# DSD_SDR_MainBoard_Simple.net
KiCad netlist of a schematic drawn in Altium Designer
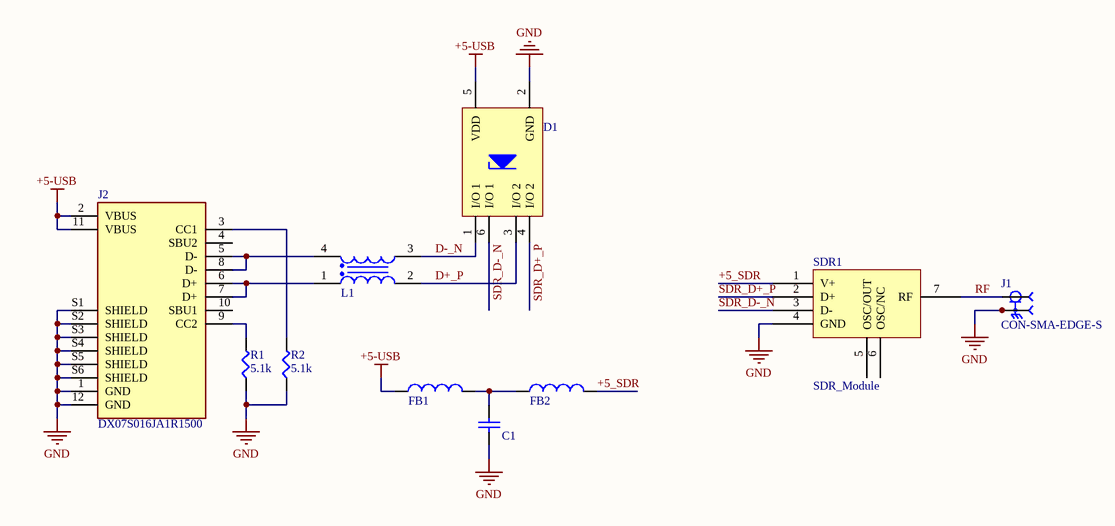
[diagram p0: DSD_SDR_MainBoard_Simple.SchDoc]

(export (version "E")
  (design (tool "Eeschema 10.0.6"))
  (components
    (comp (ref "C1")
      (value "680nF")
      (footprint "WCAP-CSGP_0603_L1.6W0.8H0.8_Reflow")
      (description "WCAP-CSGP Multilayer Ceramic Chip Capacitor, General Purpose, size 0603, X7R, 680nF, 16VDC")
      (fields
        (field (name "MANUFACTURER PART NUMBER") "885012206051")
        (field (name "MANUFACTURER") "Wurth Elektronik")
      )
      (libsource (lib "Altium_WCAP-CSGP (rev22f)") (part "885012206051"))
    )
    (comp (ref "D1")
      (value "5V")
      (footprint "WE-TVS_SOT23-6L")
      (description "WE-TVS TVS Diode – High Speed Series, SOT23-6L, 2+1 Channel, 5V, 2pF")
      (fields
        (field (name "MANUFACTURER PART NUMBER") "82400102")
        (field (name "MANUFACTURER") "Wurth Elektronik")
      )
      (libsource (lib "Altium_WE-TVS (rev22b)") (part "82400102"))
    )
    (comp (ref "FB1")
      (value "600Ohm")
      (footprint "WE-CBF_0603_L1.6W0.8H0.8_HC")
      (description "WE-CBF SMT EMI Suppression Ferrite Bead, size 0603, 600Ohm, 1A")
      (fields
        (field (name "MANUFACTURER PART NUMBER") "742792651")
        (field (name "MANUFACTURER") "Wurth Elektronik")
      )
      (libsource (lib "WE-CBF (rev22d)") (part "742792651"))
    )
    (comp (ref "FB2")
      (value "600Ohm")
      (footprint "WE-CBF_0603_L1.6W0.8H0.8_HC")
      (description "WE-CBF SMT EMI Suppression Ferrite Bead, size 0603, 600Ohm, 1A")
      (fields
        (field (name "MANUFACTURER PART NUMBER") "742792651")
        (field (name "MANUFACTURER") "Wurth Elektronik")
      )
      (libsource (lib "WE-CBF (rev22d)") (part "742792651"))
    )
    (comp (ref "J1")
      (value "CON-SMA-EDGE-S")
      (footprint "RFSOLUTIONS_CON-SMA-EDGE-S")
      (description "SMA Connector Jack, Female Socket - Board Edge, End Launch Solder")
      (fields (field (name "MF") "RF Solutions") (field (name "DIGI-KEY_PART_NUMBER") "CON-SMA-EDGE-S-ND"))
      (libsource (lib "CON-SMA-EDGE-S") (part "CON-SMA-EDGE-S"))
    )
    (comp (ref "J2")
      (value "DX07S016JA1R1500")
      (footprint "JAE_DX07S016JA1R1500")
      (fields (field (name "MF") "JAE Electronics"))
      (libsource (lib "DX07S016JA1R1500") (part "DX07S016JA1R1500"))
    )
    (comp (ref "L1")
      (value "90Ohm")
      (footprint "WE-CNSW_1206")
      (description "WE-CNSW SMT Common Mode Line Filter, size 1206, 90Ohm, 0.111uH, 50V")
      (fields
        (field (name "MANUFACTURER") "Wurth Elektronik")
        (field (name "MANUFACTURER PART NUMBER") "744232090")
      )
      (libsource (lib "WE-CNSW (rev22a)") (part "744232090"))
    )
    (comp (ref "R1")
      (value "5.1k")
      (footprint "SMD-0603-RES")
      (description "RES SMD 5.1K OHM 1% 1/10W 0603")
      (fields
        (field (name "PART NUMBER") "ERJ-3EKF5101V")
        (field (name "DIGI-KEY PART NUMBER") "P5.10KHCT-ND")
      )
      (libsource (lib "res_panasonic_erj_xls") (part "RESISTOR"))
    )
    (comp (ref "R2")
      (value "5.1k")
      (footprint "SMD-0603-RES")
      (description "RES SMD 5.1K OHM 1% 1/10W 0603")
      (fields
        (field (name "PART NUMBER") "ERJ-3EKF5101V")
        (field (name "DIGI-KEY PART NUMBER") "P5.10KHCT-ND")
      )
      (libsource (lib "res_panasonic_erj_xls") (part "RESISTOR"))
    )
    (comp (ref "SDR1")
      (value "SDR_Module")
      (footprint "SDR")
      (libsource (lib "SDR_Module") (part "SDR_Module"))
    )
  )
  (nets
    (net (code "1") (name "+5-USB") (class "Default")
      (node (ref "D1") (pin "5") (pinfunction "VDD_5") (pintype "passive"))
      (node (ref "FB1") (pin "1") (pinfunction "1_1") (pintype "passive"))
      (node (ref "J2") (pin "11") (pinfunction "VBUS_11") (pintype "power_in"))
      (node (ref "J2") (pin "2") (pinfunction "VBUS_2") (pintype "power_in"))
    )
    (net (code "2") (name "/+5_SDR") (class "Default")
      (node (ref "FB2") (pin "2") (pinfunction "2_2") (pintype "passive"))
      (node (ref "SDR1") (pin "1") (pinfunction "V+_1") (pintype "passive"))
    )
    (net (code "3") (name "/D+_P") (class "Default")
      (node (ref "D1") (pin "3") (pinfunction "I/O_2_3") (pintype "passive"))
      (node (ref "L1") (pin "2") (pinfunction "2_2") (pintype "passive"))
    )
    (net (code "4") (name "/D-_N") (class "Default")
      (node (ref "D1") (pin "1") (pinfunction "I/O_1_1") (pintype "passive"))
      (node (ref "L1") (pin "3") (pinfunction "3_3") (pintype "passive"))
    )
    (net (code "5") (name "/RF") (class "Default")
      (node (ref "J1") (pin "1") (pinfunction "1_1") (pintype "passive"))
      (node (ref "SDR1") (pin "7") (pinfunction "RF_7") (pintype "passive"))
    )
    (net (code "6") (name "/SDR_D+_P") (class "Default")
      (node (ref "D1") (pin "4") (pinfunction "I/O_2_4") (pintype "passive"))
      (node (ref "SDR1") (pin "2") (pinfunction "D+_2") (pintype "passive"))
    )
    (net (code "7") (name "/SDR_D-_N") (class "Default")
      (node (ref "D1") (pin "6") (pinfunction "I/O_1_6") (pintype "passive"))
      (node (ref "SDR1") (pin "3") (pinfunction "D-_3") (pintype "passive"))
    )
    (net (code "8") (name "GND") (class "Default")
      (node (ref "C1") (pin "1") (pinfunction "1_1") (pintype "passive"))
      (node (ref "D1") (pin "2") (pinfunction "GND_2") (pintype "passive"))
      (node (ref "J1") (pin "G1") (pinfunction "2_G1") (pintype "passive"))
      (node (ref "J1") (pin "G2") (pinfunction "2_G2") (pintype "passive"))
      (node (ref "J1") (pin "G3") (pinfunction "2_G3") (pintype "passive"))
      (node (ref "J1") (pin "G4") (pinfunction "2_G4") (pintype "passive"))
      (node (ref "J2") (pin "1") (pinfunction "GND_1") (pintype "power_in"))
      (node (ref "J2") (pin "12") (pinfunction "GND_12") (pintype "power_in"))
      (node (ref "J2") (pin "S1") (pinfunction "SHIELD_S1") (pintype "passive"))
      (node (ref "J2") (pin "S2") (pinfunction "SHIELD_S2") (pintype "passive"))
      (node (ref "J2") (pin "S3") (pinfunction "SHIELD_S3") (pintype "passive"))
      (node (ref "J2") (pin "S4") (pinfunction "SHIELD_S4") (pintype "passive"))
      (node (ref "J2") (pin "S5") (pinfunction "SHIELD_S5") (pintype "passive"))
      (node (ref "J2") (pin "S6") (pinfunction "SHIELD_S6") (pintype "passive"))
      (node (ref "R1") (pin "1") (pinfunction "1_1") (pintype "passive"))
      (node (ref "R2") (pin "1") (pinfunction "1_1") (pintype "passive"))
      (node (ref "SDR1") (pin "4") (pinfunction "GND_4") (pintype "passive"))
    )
    (net (code "9") (name "Net-(C1-Pad2)") (class "Default")
      (node (ref "C1") (pin "2") (pinfunction "2_2") (pintype "passive"))
      (node (ref "FB1") (pin "2") (pinfunction "2_2") (pintype "passive"))
      (node (ref "FB2") (pin "1") (pinfunction "1_1") (pintype "passive"))
    )
    (net (code "10") (name "Net-(J2-CC1)") (class "Default")
      (node (ref "J2") (pin "3") (pinfunction "CC1_3") (pintype "passive"))
      (node (ref "R2") (pin "2") (pinfunction "2_2") (pintype "passive"))
    )
    (net (code "11") (name "Net-(J2-CC2)") (class "Default")
      (node (ref "J2") (pin "9") (pinfunction "CC2_9") (pintype "passive"))
      (node (ref "R1") (pin "2") (pinfunction "2_2") (pintype "passive"))
    )
    (net (code "12") (name "Net-(J2-D+-Pad6)") (class "Default")
      (node (ref "J2") (pin "6") (pinfunction "D+_6") (pintype "passive"))
      (node (ref "J2") (pin "7") (pinfunction "D+_7") (pintype "passive"))
      (node (ref "L1") (pin "1") (pinfunction "1_1") (pintype "passive"))
    )
    (net (code "13") (name "Net-(J2-D--Pad5)") (class "Default")
      (node (ref "J2") (pin "5") (pinfunction "D-_5") (pintype "passive"))
      (node (ref "J2") (pin "8") (pinfunction "D-_8") (pintype "passive"))
      (node (ref "L1") (pin "4") (pinfunction "4_4") (pintype "passive"))
    )
    (net (code "14") (name "unconnected-(J2-SBU1-Pad10)") (class "Default")
      (node (ref "J2") (pin "10") (pinfunction "SBU1_10") (pintype "passive"))
    )
    (net (code "15") (name "unconnected-(J2-SBU2-Pad4)") (class "Default")
      (node (ref "J2") (pin "4") (pinfunction "SBU2_4") (pintype "passive"))
    )
    (net (code "16") (name "unconnected-(SDR1-OSC{slash}NC-Pad6)") (class "Default")
      (node (ref "SDR1") (pin "6") (pinfunction "OSC/NC_6") (pintype "passive"))
    )
    (net (code "17") (name "unconnected-(SDR1-OSC{slash}OUT-Pad5)") (class "Default")
      (node (ref "SDR1") (pin "5") (pinfunction "OSC/OUT_5") (pintype "passive"))
    )
  )
)
